# MTRduino_Rev3_0.net
KiCad netlist of a schematic drawn in EAGLE
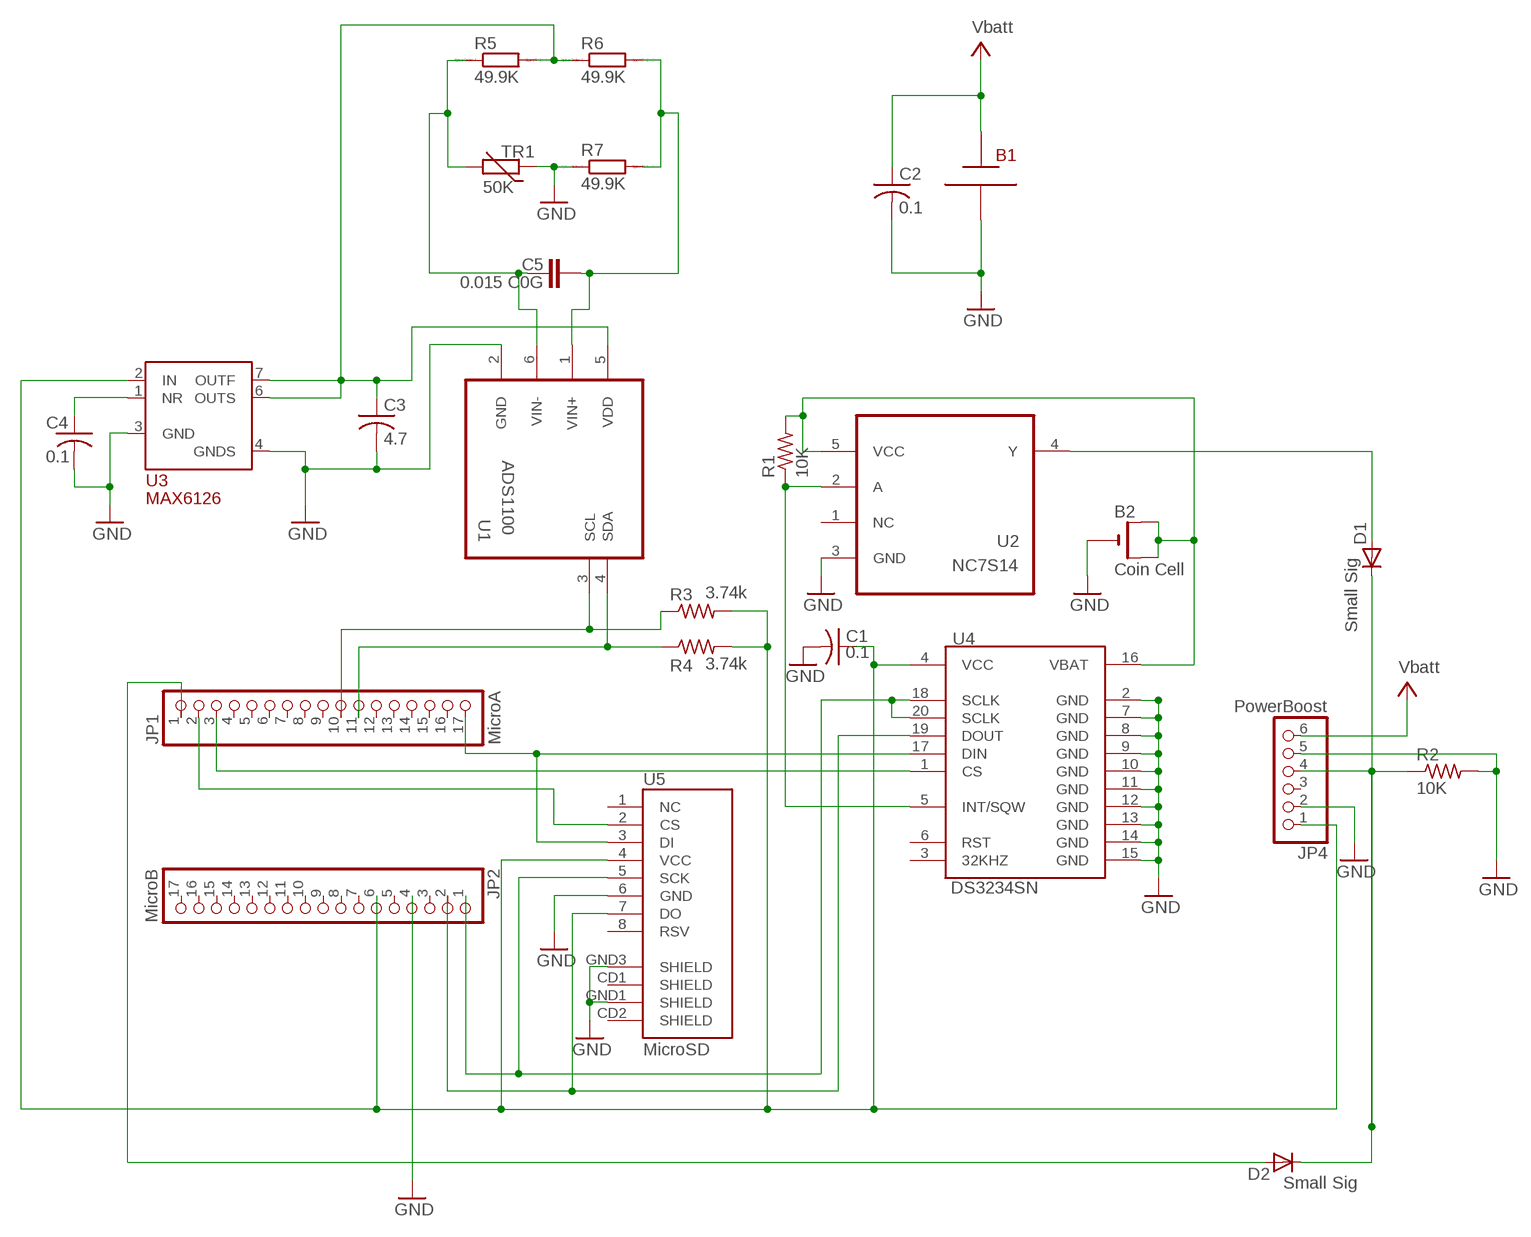
[diagram p0: schematic, sheet 1]

(export (version "E")
  (design (tool "Eeschema 10.0.6"))
  (components
    (comp (ref "B1")
      (value "2x AA BATT")
      (footprint "eagle-import:BATT_AA2")
      (libsource (lib "eagle-import") (part "BATT_AA2"))
    )
    (comp (ref "B2")
      (value "Coin Cell")
      (footprint "eagle-import:CR1220-SMD")
      (libsource (lib "eagle-import") (part "CR1220SMT"))
    )
    (comp (ref "C1")
      (value "0.1")
      (footprint "eagle-import:C0603")
      (libsource (lib "eagle-import") (part "C-USC0603"))
    )
    (comp (ref "C2")
      (value "0.1")
      (footprint "eagle-import:C0603")
      (libsource (lib "eagle-import") (part "C-USC0603"))
    )
    (comp (ref "C3")
      (value "4.7")
      (footprint "eagle-import:C0603")
      (libsource (lib "eagle-import") (part "C-USC0603"))
    )
    (comp (ref "C4")
      (value "0.1")
      (footprint "eagle-import:C0603")
      (libsource (lib "eagle-import") (part "C-USC0603"))
    )
    (comp (ref "C5")
      (value "0.015 C0G")
      (footprint "eagle-import:C0603")
      (libsource (lib "eagle-import") (part "C-EUC0603"))
    )
    (comp (ref "D1")
      (value "Small Sig")
      (footprint "eagle-import:SOD-323F")
      (libsource (lib "eagle-import") (part "DIODESOD-323F"))
    )
    (comp (ref "D2")
      (value "Small Sig")
      (footprint "eagle-import:SOD-323F")
      (libsource (lib "eagle-import") (part "DIODESOD-323F"))
    )
    (comp (ref "JP1")
      (value "MicroA")
      (footprint "eagle-import:1X17")
      (libsource (lib "eagle-import") (part "PINHD-1X17"))
    )
    (comp (ref "JP2")
      (value "MicroB")
      (footprint "eagle-import:1X17")
      (libsource (lib "eagle-import") (part "PINHD-1X17"))
    )
    (comp (ref "JP4")
      (value "PowerBoost")
      (footprint "eagle-import:1X06")
      (libsource (lib "eagle-import") (part "PINHD-1X6"))
    )
    (comp (ref "R1")
      (value "10K")
      (footprint "eagle-import:R0603")
      (libsource (lib "eagle-import") (part "R-US_R0603"))
    )
    (comp (ref "R2")
      (value "10K")
      (footprint "eagle-import:R0603")
      (libsource (lib "eagle-import") (part "R-US_R0603"))
    )
    (comp (ref "R3")
      (value "3.74k")
      (footprint "eagle-import:R0603")
      (libsource (lib "eagle-import") (part "R-US_R0603"))
    )
    (comp (ref "R4")
      (value "3.74k")
      (footprint "eagle-import:R0603")
      (libsource (lib "eagle-import") (part "R-US_R0603"))
    )
    (comp (ref "R5")
      (value "49.9K")
      (footprint "eagle-import:R3216")
      (libsource (lib "eagle-import") (part "RR3216"))
    )
    (comp (ref "R6")
      (value "49.9K")
      (footprint "eagle-import:R3216")
      (libsource (lib "eagle-import") (part "RR3216"))
    )
    (comp (ref "R7")
      (value "49.9K")
      (footprint "eagle-import:R3216")
      (libsource (lib "eagle-import") (part "RR3216"))
    )
    (comp (ref "TR1")
      (value "50K")
      (footprint "eagle-import:R-5")
      (libsource (lib "eagle-import") (part "THERMISTOR_R-5"))
    )
    (comp (ref "U1")
      (value "ADS1100")
      (footprint "eagle-import:SOT95P280X145-6N")
      (fields (field (name "MPN") "ADS1100A0IDBVT"))
      (libsource (lib "eagle-import") (part "ADS1100A0IDBVT"))
    )
    (comp (ref "U2")
      (value "NC7S14")
      (footprint "eagle-import:SOT95P280X145-5N")
      (fields (field (name "MPN") "1P1G14MDBVREPG4"))
      (libsource (lib "eagle-import") (part "1P1G14MDBVREPG4"))
    )
    (comp (ref "U3")
      (value "MAX6126")
      (footprint "eagle-import:SOIC127P600X175-8N")
      (libsource (lib "eagle-import") (part "MAX6126"))
    )
    (comp (ref "U4")
      (value "DS3234SN")
      (footprint "eagle-import:DS3234")
      (libsource (lib "eagle-import") (part "DS3234"))
    )
    (comp (ref "U5")
      (value "MicroSD")
      (footprint "eagle-import:MICRO-SD-SOCKET-PP")
      (libsource (lib "eagle-import") (part "USD-SOCKETNEW"))
    )
  )
  (nets
    (net (code "1") (name "GND") (class "Default")
      (node (ref "B1") (pin "-") (pinfunction "-_-") (pintype "bidirectional"))
      (node (ref "B2") (pin "-") (pinfunction "-_-") (pintype "passive"))
      (node (ref "C1") (pin "2") (pinfunction "2_2") (pintype "passive"))
      (node (ref "C2") (pin "2") (pinfunction "2_2") (pintype "passive"))
      (node (ref "C3") (pin "2") (pinfunction "2_2") (pintype "passive"))
      (node (ref "C4") (pin "2") (pinfunction "2_2") (pintype "passive"))
      (node (ref "JP2") (pin "4") (pinfunction "4_4") (pintype "passive"))
      (node (ref "JP4") (pin "2") (pinfunction "2_2") (pintype "passive"))
      (node (ref "JP4") (pin "5") (pinfunction "5_5") (pintype "passive"))
      (node (ref "R2") (pin "2") (pinfunction "2_2") (pintype "passive"))
      (node (ref "R7") (pin "1") (pinfunction "1_1") (pintype "passive"))
      (node (ref "TR1") (pin "1") (pinfunction "1_1") (pintype "passive"))
      (node (ref "U1") (pin "2") (pinfunction "GND_2") (pintype "passive"))
      (node (ref "U2") (pin "3") (pinfunction "GND_3") (pintype "passive"))
      (node (ref "U3") (pin "3") (pinfunction "GND_3") (pintype "input"))
      (node (ref "U3") (pin "4") (pinfunction "GNDS_4") (pintype "input"))
      (node (ref "U4") (pin "10") (pinfunction "GND_10") (pintype "bidirectional"))
      (node (ref "U4") (pin "11") (pinfunction "GND_11") (pintype "bidirectional"))
      (node (ref "U4") (pin "12") (pinfunction "GND_12") (pintype "bidirectional"))
      (node (ref "U4") (pin "13") (pinfunction "GND_13") (pintype "bidirectional"))
      (node (ref "U4") (pin "14") (pinfunction "GND_14") (pintype "bidirectional"))
      (node (ref "U4") (pin "15") (pinfunction "GND_15") (pintype "bidirectional"))
      (node (ref "U4") (pin "2") (pinfunction "GND_2") (pintype "bidirectional"))
      (node (ref "U4") (pin "7") (pinfunction "GND_7") (pintype "bidirectional"))
      (node (ref "U4") (pin "8") (pinfunction "GND_8") (pintype "bidirectional"))
      (node (ref "U4") (pin "9") (pinfunction "GND_9") (pintype "bidirectional"))
      (node (ref "U5") (pin "6") (pinfunction "GND_6") (pintype "bidirectional"))
      (node (ref "U5") (pin "GND1") (pinfunction "SHIELD_GND1") (pintype "bidirectional"))
      (node (ref "U5") (pin "GND3") (pinfunction "SHIELD_GND3") (pintype "bidirectional"))
    )
    (net (code "2") (name "Net-(B2-+)") (class "Default")
      (node (ref "B2") (pin "+$1") (pinfunction "+_+$1") (pintype "passive"))
      (node (ref "B2") (pin "+$2") (pinfunction "+1_+$2") (pintype "passive"))
      (node (ref "R1") (pin "2") (pinfunction "2_2") (pintype "passive"))
      (node (ref "U2") (pin "5") (pinfunction "VCC_5") (pintype "power_in"))
      (node (ref "U4") (pin "16") (pinfunction "VBAT_16") (pintype "bidirectional"))
    )
    (net (code "3") (name "Net-(D1-PadC)") (class "Default")
      (node (ref "D1") (pin "C") (pinfunction "C_C") (pintype "passive"))
      (node (ref "D2") (pin "C") (pinfunction "C_C") (pintype "passive"))
      (node (ref "JP4") (pin "4") (pinfunction "4_4") (pintype "passive"))
      (node (ref "R2") (pin "1") (pinfunction "1_1") (pintype "passive"))
    )
    (net (code "4") (name "Net-(D2-PadA)") (class "Default")
      (node (ref "D2") (pin "A") (pinfunction "A_A") (pintype "passive"))
      (node (ref "JP1") (pin "1") (pinfunction "1_1") (pintype "passive"))
    )
    (net (code "5") (name "Net-(U1-SCL)") (class "Default")
      (node (ref "JP1") (pin "10") (pinfunction "10_10") (pintype "passive"))
      (node (ref "R3") (pin "1") (pinfunction "1_1") (pintype "passive"))
      (node (ref "U1") (pin "3") (pinfunction "SCL_3") (pintype "output"))
    )
    (net (code "6") (name "Net-(U1-SDA)") (class "Default")
      (node (ref "JP1") (pin "11") (pinfunction "11_11") (pintype "passive"))
      (node (ref "R4") (pin "1") (pinfunction "1_1") (pintype "passive"))
      (node (ref "U1") (pin "4") (pinfunction "SDA_4") (pintype "output"))
    )
    (net (code "7") (name "Net-(U1-VDD)") (class "Default")
      (node (ref "C3") (pin "1") (pinfunction "1_1") (pintype "passive"))
      (node (ref "R5") (pin "2") (pinfunction "2_2") (pintype "passive"))
      (node (ref "R6") (pin "1") (pinfunction "1_1") (pintype "passive"))
      (node (ref "U1") (pin "5") (pinfunction "VDD_5") (pintype "power_in"))
      (node (ref "U3") (pin "6") (pinfunction "OUTS_6") (pintype "output"))
      (node (ref "U3") (pin "7") (pinfunction "OUTF_7") (pintype "output"))
    )
    (net (code "8") (name "Net-(U1-VIN+)") (class "Default")
      (node (ref "C5") (pin "2") (pinfunction "2_2") (pintype "passive"))
      (node (ref "R6") (pin "2") (pinfunction "2_2") (pintype "passive"))
      (node (ref "R7") (pin "2") (pinfunction "2_2") (pintype "passive"))
      (node (ref "U1") (pin "1") (pinfunction "VIN+_1") (pintype "input"))
    )
    (net (code "9") (name "Net-(U1-VIN-)") (class "Default")
      (node (ref "C5") (pin "1") (pinfunction "1_1") (pintype "passive"))
      (node (ref "R5") (pin "1") (pinfunction "1_1") (pintype "passive"))
      (node (ref "TR1") (pin "2") (pinfunction "2_2") (pintype "passive"))
      (node (ref "U1") (pin "6") (pinfunction "VIN-_6") (pintype "input"))
    )
    (net (code "10") (name "Net-(U2-A)") (class "Default")
      (node (ref "R1") (pin "1") (pinfunction "1_1") (pintype "passive"))
      (node (ref "U2") (pin "2") (pinfunction "A_2") (pintype "input"))
      (node (ref "U4") (pin "5") (pinfunction "INT/SQW_5") (pintype "bidirectional"))
    )
    (net (code "11") (name "Net-(U2-Y)") (class "Default")
      (node (ref "D1") (pin "A") (pinfunction "A_A") (pintype "passive"))
      (node (ref "U2") (pin "4") (pinfunction "Y_4") (pintype "output"))
    )
    (net (code "12") (name "Net-(U3-IN)") (class "Default")
      (node (ref "C1") (pin "1") (pinfunction "1_1") (pintype "passive"))
      (node (ref "JP2") (pin "6") (pinfunction "6_6") (pintype "passive"))
      (node (ref "JP4") (pin "1") (pinfunction "1_1") (pintype "passive"))
      (node (ref "R3") (pin "2") (pinfunction "2_2") (pintype "passive"))
      (node (ref "R4") (pin "2") (pinfunction "2_2") (pintype "passive"))
      (node (ref "U3") (pin "2") (pinfunction "IN_2") (pintype "input"))
      (node (ref "U4") (pin "4") (pinfunction "VCC_4") (pintype "bidirectional"))
      (node (ref "U5") (pin "4") (pinfunction "VCC_4") (pintype "bidirectional"))
    )
    (net (code "13") (name "Net-(U3-NR)") (class "Default")
      (node (ref "C4") (pin "1") (pinfunction "1_1") (pintype "passive"))
      (node (ref "U3") (pin "1") (pinfunction "NR_1") (pintype "bidirectional"))
    )
    (net (code "14") (name "Net-(U4-CS)") (class "Default")
      (node (ref "JP1") (pin "3") (pinfunction "3_3") (pintype "passive"))
      (node (ref "U4") (pin "1") (pinfunction "CS_1") (pintype "bidirectional"))
    )
    (net (code "15") (name "Net-(U4-DIN)") (class "Default")
      (node (ref "JP1") (pin "17") (pinfunction "17_17") (pintype "passive"))
      (node (ref "U4") (pin "17") (pinfunction "DIN_17") (pintype "bidirectional"))
      (node (ref "U5") (pin "3") (pinfunction "DI_3") (pintype "bidirectional"))
    )
    (net (code "16") (name "Net-(U4-DOUT)") (class "Default")
      (node (ref "JP2") (pin "2") (pinfunction "2_2") (pintype "passive"))
      (node (ref "U4") (pin "19") (pinfunction "DOUT_19") (pintype "bidirectional"))
      (node (ref "U5") (pin "7") (pinfunction "DO_7") (pintype "bidirectional"))
    )
    (net (code "17") (name "Net-(U5-CS)") (class "Default")
      (node (ref "JP1") (pin "2") (pinfunction "2_2") (pintype "passive"))
      (node (ref "U5") (pin "2") (pinfunction "CS_2") (pintype "bidirectional"))
    )
    (net (code "18") (name "Net-(U5-SCK)") (class "Default")
      (node (ref "JP2") (pin "1") (pinfunction "1_1") (pintype "passive"))
      (node (ref "U4") (pin "18") (pinfunction "SCLK_18") (pintype "bidirectional"))
      (node (ref "U4") (pin "20") (pinfunction "SCLK_20") (pintype "bidirectional"))
      (node (ref "U5") (pin "5") (pinfunction "SCK_5") (pintype "bidirectional"))
    )
    (net (code "19") (name "Vbatt") (class "Default")
      (node (ref "B1") (pin "+") (pinfunction "+_+") (pintype "bidirectional"))
      (node (ref "C2") (pin "1") (pinfunction "1_1") (pintype "passive"))
      (node (ref "JP4") (pin "6") (pinfunction "6_6") (pintype "passive"))
    )
    (net (code "20") (name "unconnected-(JP1-Pad4)") (class "Default")
      (node (ref "JP1") (pin "4") (pinfunction "4_4") (pintype "passive"))
    )
    (net (code "21") (name "unconnected-(JP1-Pad5)") (class "Default")
      (node (ref "JP1") (pin "5") (pinfunction "5_5") (pintype "passive"))
    )
    (net (code "22") (name "unconnected-(JP1-Pad6)") (class "Default")
      (node (ref "JP1") (pin "6") (pinfunction "6_6") (pintype "passive"))
    )
    (net (code "23") (name "unconnected-(JP1-Pad7)") (class "Default")
      (node (ref "JP1") (pin "7") (pinfunction "7_7") (pintype "passive"))
    )
    (net (code "24") (name "unconnected-(JP1-Pad8)") (class "Default")
      (node (ref "JP1") (pin "8") (pinfunction "8_8") (pintype "passive"))
    )
    (net (code "25") (name "unconnected-(JP1-Pad9)") (class "Default")
      (node (ref "JP1") (pin "9") (pinfunction "9_9") (pintype "passive"))
    )
    (net (code "26") (name "unconnected-(JP1-Pad12)") (class "Default")
      (node (ref "JP1") (pin "12") (pinfunction "12_12") (pintype "passive"))
    )
    (net (code "27") (name "unconnected-(JP1-Pad13)") (class "Default")
      (node (ref "JP1") (pin "13") (pinfunction "13_13") (pintype "passive"))
    )
    (net (code "28") (name "unconnected-(JP1-Pad14)") (class "Default")
      (node (ref "JP1") (pin "14") (pinfunction "14_14") (pintype "passive"))
    )
    (net (code "29") (name "unconnected-(JP1-Pad15)") (class "Default")
      (node (ref "JP1") (pin "15") (pinfunction "15_15") (pintype "passive"))
    )
    (net (code "30") (name "unconnected-(JP1-Pad16)") (class "Default")
      (node (ref "JP1") (pin "16") (pinfunction "16_16") (pintype "passive"))
    )
    (net (code "31") (name "unconnected-(JP2-Pad3)") (class "Default")
      (node (ref "JP2") (pin "3") (pinfunction "3_3") (pintype "passive"))
    )
    (net (code "32") (name "unconnected-(JP2-Pad5)") (class "Default")
      (node (ref "JP2") (pin "5") (pinfunction "5_5") (pintype "passive"))
    )
    (net (code "33") (name "unconnected-(JP2-Pad7)") (class "Default")
      (node (ref "JP2") (pin "7") (pinfunction "7_7") (pintype "passive"))
    )
    (net (code "34") (name "unconnected-(JP2-Pad8)") (class "Default")
      (node (ref "JP2") (pin "8") (pinfunction "8_8") (pintype "passive"))
    )
    (net (code "35") (name "unconnected-(JP2-Pad9)") (class "Default")
      (node (ref "JP2") (pin "9") (pinfunction "9_9") (pintype "passive"))
    )
    (net (code "36") (name "unconnected-(JP2-Pad10)") (class "Default")
      (node (ref "JP2") (pin "10") (pinfunction "10_10") (pintype "passive"))
    )
    (net (code "37") (name "unconnected-(JP2-Pad11)") (class "Default")
      (node (ref "JP2") (pin "11") (pinfunction "11_11") (pintype "passive"))
    )
    (net (code "38") (name "unconnected-(JP2-Pad12)") (class "Default")
      (node (ref "JP2") (pin "12") (pinfunction "12_12") (pintype "passive"))
    )
    (net (code "39") (name "unconnected-(JP2-Pad13)") (class "Default")
      (node (ref "JP2") (pin "13") (pinfunction "13_13") (pintype "passive"))
    )
    (net (code "40") (name "unconnected-(JP2-Pad14)") (class "Default")
      (node (ref "JP2") (pin "14") (pinfunction "14_14") (pintype "passive"))
    )
    (net (code "41") (name "unconnected-(JP2-Pad15)") (class "Default")
      (node (ref "JP2") (pin "15") (pinfunction "15_15") (pintype "passive"))
    )
    (net (code "42") (name "unconnected-(JP2-Pad16)") (class "Default")
      (node (ref "JP2") (pin "16") (pinfunction "16_16") (pintype "passive"))
    )
    (net (code "43") (name "unconnected-(JP2-Pad17)") (class "Default")
      (node (ref "JP2") (pin "17") (pinfunction "17_17") (pintype "passive"))
    )
    (net (code "44") (name "unconnected-(JP4-Pad3)") (class "Default")
      (node (ref "JP4") (pin "3") (pinfunction "3_3") (pintype "passive"))
    )
    (net (code "45") (name "unconnected-(U2-NC-Pad1)") (class "Default")
      (node (ref "U2") (pin "1") (pinfunction "NC_1") (pintype "no_connect"))
    )
    (net (code "46") (name "unconnected-(U4-32KHZ-Pad3)") (class "Default")
      (node (ref "U4") (pin "3") (pinfunction "32KHZ_3") (pintype "bidirectional"))
    )
    (net (code "47") (name "unconnected-(U4-RST-Pad6)") (class "Default")
      (node (ref "U4") (pin "6") (pinfunction "RST_6") (pintype "bidirectional"))
    )
    (net (code "48") (name "unconnected-(U5-NC-Pad1)") (class "Default")
      (node (ref "U5") (pin "1") (pinfunction "NC_1") (pintype "bidirectional"))
    )
    (net (code "49") (name "unconnected-(U5-RSV-Pad8)") (class "Default")
      (node (ref "U5") (pin "8") (pinfunction "RSV_8") (pintype "bidirectional"))
    )
    (net (code "50") (name "unconnected-(U5-SHIELD-PadCD1)") (class "Default")
      (node (ref "U5") (pin "CD1") (pinfunction "SHIELD_CD1") (pintype "bidirectional"))
    )
    (net (code "51") (name "unconnected-(U5-SHIELD-PadCD2)") (class "Default")
      (node (ref "U5") (pin "CD2") (pinfunction "SHIELD_CD2") (pintype "bidirectional"))
    )
  )
)
